# osc.net
KiCad netlist of a schematic drawn in Altium Designer
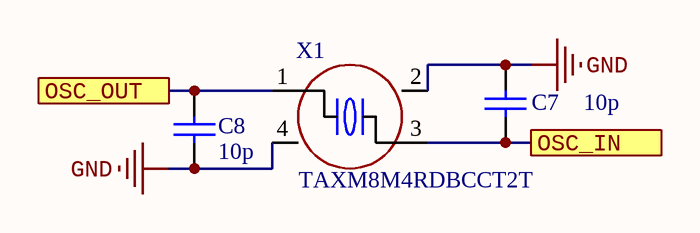
[diagram p0: osc.SchDoc]

(export (version "E")
  (design (tool "Eeschema 10.0.6"))
  (components
    (comp (ref "C7")
      (value "10p")
      (footprint "footprints:CAPC100X50X55L25N")
      (fields
        (field (name "MPN") "CC0402JRNPO9BN100")
        (field (name "MANUFACTURER") "YAGEO(国巨)")
        (field (name "Comment") "Capacitor")
      )
      (libsource (lib "std_lib") (part "Capacitor"))
    )
    (comp (ref "C8")
      (value "10p")
      (footprint "footprints:CAPC100X50X55L25N")
      (fields
        (field (name "MPN") "CC0402JRNPO9BN100")
        (field (name "MANUFACTURER") "YAGEO(国巨)")
        (field (name "Comment") "Capacitor")
      )
      (libsource (lib "std_lib") (part "Capacitor"))
    )
    (comp (ref "X1")
      (value "TAXM8M4RDBCCT2T")
      (footprint "footprints:OSCCC320X250X80L90X100N")
      (description "8MHz ±10ppm 10pF")
      (fields (field (name "MANUFACTURER") "TAE(雅晶鑫)"))
      (libsource (lib "mcontroller") (part "X32258MSB4SI"))
    )
  )
  (nets
    (net (code "1") (name "/OSC_IN") (class "Default")
      (node (ref "C7") (pin "1") (pinfunction "1_1") (pintype "passive"))
      (node (ref "X1") (pin "3") (pinfunction "3_3") (pintype "passive"))
    )
    (net (code "2") (name "/OSC_OUT") (class "Default")
      (node (ref "C8") (pin "2") (pinfunction "2_2") (pintype "passive"))
      (node (ref "X1") (pin "1") (pinfunction "1_1") (pintype "passive"))
    )
    (net (code "3") (name "GND") (class "Default")
      (node (ref "C7") (pin "2") (pinfunction "2_2") (pintype "passive"))
      (node (ref "C8") (pin "1") (pinfunction "1_1") (pintype "passive"))
      (node (ref "X1") (pin "2") (pinfunction "GND_2") (pintype "passive"))
      (node (ref "X1") (pin "4") (pinfunction "GND_4") (pintype "passive"))
    )
  )
)
